# ottoesp-2s-wrover.net
KiCad netlist of a schematic drawn in EAGLE
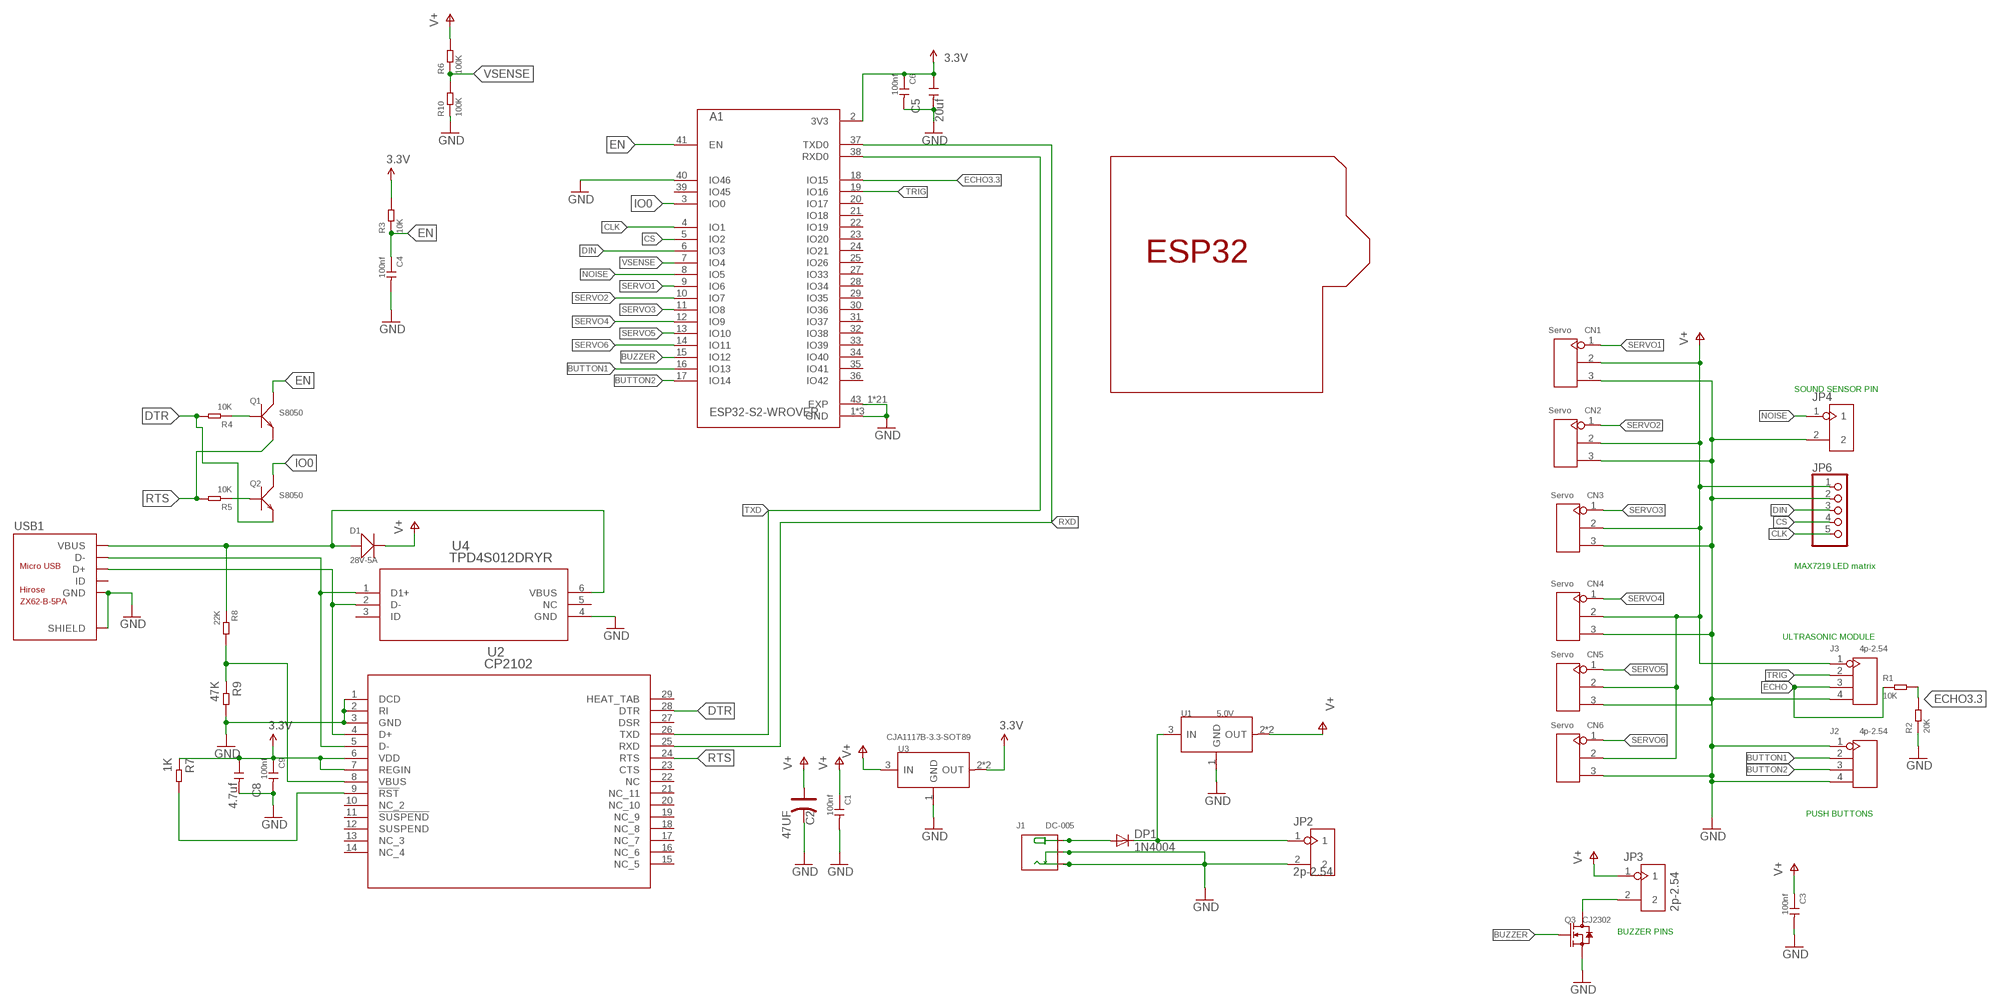
[diagram p0: schematic, sheet 1]

(export (version "E")
  (design (tool "Eeschema 10.0.6"))
  (components
    (comp (ref "A1")
      (value "ESP32-S2-WROVER")
      (footprint "eagle-import:MODULE_ESP32-S2-WROVER")
      (fields (field (name "MF") "Espressif Systems"))
      (libsource (lib "eagle-import") (part "ESP32-S2-WROVER"))
    )
    (comp (ref "C1")
      (value "100nf")
      (footprint "eagle-import:C0805")
      (fields (field (name "MPN") "CC0805KRX7R9BB104"))
      (libsource (lib "eagle-import") (part "CERAMIC-100NF-50V-10%-X7R(0805)"))
    )
    (comp (ref "C2")
      (value "47UF")
      (footprint "eagle-import:ELECTRO-SMD-C-6MM")
      (fields (field (name "MPN") "CS1E470M-CRE54"))
      (libsource (lib "eagle-import") (part "ALUMINUM-SMD-47UF-25V(D6.3-H5.3MM)"))
    )
    (comp (ref "C3")
      (value "100nf")
      (footprint "eagle-import:C0805")
      (fields (field (name "MPN") "CC0805KRX7R9BB104"))
      (libsource (lib "eagle-import") (part "Seeed-Capacitor_CERAMIC-100NF-50V-10%-X7R(0805)"))
    )
    (comp (ref "C4")
      (value "100nf")
      (footprint "eagle-import:C0805")
      (fields (field (name "MPN") "CC0805KRX7R9BB104"))
      (libsource (lib "eagle-import") (part "CERAMIC-100NF-50V-10%-X7R(0805)"))
    )
    (comp (ref "C5")
      (value "20uf")
      (footprint "eagle-import:C1206")
      (libsource (lib "eagle-import") (part "CERAMIC-22UF-16V-10%-X7R(1206)"))
    )
    (comp (ref "C6")
      (value "100nf")
      (footprint "eagle-import:C0805")
      (fields (field (name "MPN") "CC0805KRX7R9BB104"))
      (libsource (lib "eagle-import") (part "CERAMIC-100NF-50V-10%-X7R(0805)"))
    )
    (comp (ref "C8")
      (value "4.7uf")
      (footprint "eagle-import:C0805")
      (fields (field (name "MPN") "CC0805KKX5R8BB475"))
      (libsource (lib "eagle-import") (part "CERAMIC-4.7UF-25V-10%-X5R(0805)"))
    )
    (comp (ref "C9")
      (value "100nf")
      (footprint "eagle-import:C0805")
      (fields (field (name "MPN") "CC0805KRX7R9BB104"))
      (libsource (lib "eagle-import") (part "CERAMIC-100NF-50V-10%-X7R(0805)"))
    )
    (comp (ref "CN1")
      (value "Servo")
      (footprint "eagle-import:H3-2.54")
      (libsource (lib "eagle-import") (part "DIP-BLACK-MALE-HEADER-VERT(3P-2.54)"))
    )
    (comp (ref "CN2")
      (value "Servo")
      (footprint "eagle-import:H3-2.54")
      (libsource (lib "eagle-import") (part "DIP-BLACK-MALE-HEADER-VERT(3P-2.54)"))
    )
    (comp (ref "CN3")
      (value "Servo")
      (footprint "eagle-import:H3-2.54")
      (libsource (lib "eagle-import") (part "DIP-BLACK-MALE-HEADER-VERT(3P-2.54)"))
    )
    (comp (ref "CN4")
      (value "Servo")
      (footprint "eagle-import:H3-2.54")
      (libsource (lib "eagle-import") (part "DIP-BLACK-MALE-HEADER-VERT(3P-2.54)"))
    )
    (comp (ref "CN5")
      (value "Servo")
      (footprint "eagle-import:H3-2.54")
      (libsource (lib "eagle-import") (part "DIP-BLACK-MALE-HEADER-VERT(3P-2.54)"))
    )
    (comp (ref "CN6")
      (value "Servo")
      (footprint "eagle-import:H3-2.54")
      (libsource (lib "eagle-import") (part "DIP-BLACK-MALE-HEADER-VERT(3P-2.54)"))
    )
    (comp (ref "D1")
      (value "28V-5A")
      (footprint "eagle-import:DO-214AA")
      (fields (field (name "MPN") "SS54B"))
      (libsource (lib "eagle-import") (part "SMD-DIODE-SCHOTTKY-28V-5A(DO-214AA)"))
    )
    (comp (ref "DP1")
      (value "1N4004")
      (footprint "eagle-import:DO41-10")
      (libsource (lib "eagle-import") (part "1N4004"))
    )
    (comp (ref "J1")
      (value "DC-005")
      (footprint "eagle-import:DCJ3P-14.2X11.0X9.0MM")
      (libsource (lib "eagle-import") (part "CONN-POWER-JACK-2.1MM(DC-005)"))
    )
    (comp (ref "J2")
      (value "4p-2.54")
      (footprint "eagle-import:H4-2.54")
      (fields (field (name "MPN") "P125-1104A0BS116A1"))
      (libsource (lib "eagle-import") (part "DIP-BLACK-MALE-HEADER-VERT(4P-2.54)"))
    )
    (comp (ref "J3")
      (value "4p-2.54")
      (footprint "eagle-import:H4-2.54")
      (fields (field (name "MPN") "P125-1104A0BS116A1"))
      (libsource (lib "eagle-import") (part "DIP-BLACK-MALE-HEADER-VERT(4P-2.54)"))
    )
    (comp (ref "JP2")
      (value "2p-2.54")
      (footprint "eagle-import:H2-2.54")
      (fields (field (name "MPN") "P125-1102A0BS116A1"))
      (libsource (lib "eagle-import") (part "DIP-BLACK-MALE-HEADER-VERT(2P-2.54)"))
    )
    (comp (ref "JP3")
      (value "2p-2.54")
      (footprint "eagle-import:H2-2.54")
      (fields (field (name "MPN") "P125-1102A0BS116A1"))
      (libsource (lib "eagle-import") (part "DIP-BLACK-MALE-HEADER-VERT(2P-2.54)"))
    )
    (comp (ref "JP4")
      (value "2p-2.54")
      (footprint "eagle-import:H2-2.54")
      (fields (field (name "MPN") "P125-1102A0BS116A1"))
      (libsource (lib "eagle-import") (part "DIP-BLACK-MALE-HEADER-VERT(2P-2.54)"))
    )
    (comp (ref "JP6")
      (value "PINHD-1X5")
      (footprint "eagle-import:1X05")
      (libsource (lib "eagle-import") (part "PINHD-1X5"))
    )
    (comp (ref "Q1")
      (value "S8050")
      (footprint "eagle-import:SOT-23")
      (libsource (lib "eagle-import") (part "SMD-TRANSISTORS-NPN-25V-500MW-S8050(SOT-23)"))
    )
    (comp (ref "Q2")
      (value "S8050")
      (footprint "eagle-import:SOT-23")
      (libsource (lib "eagle-import") (part "SMD-TRANSISTORS-NPN-25V-500MW-S8050(SOT-23)"))
    )
    (comp (ref "Q3")
      (value "CJ2302")
      (footprint "eagle-import:SOT-23")
      (libsource (lib "eagle-import") (part "SMD-MOSFET-N-CH-20V-2.1A-CJ2302(SOT-23)"))
    )
    (comp (ref "R1")
      (value "10K")
      (footprint "eagle-import:R0805")
      (fields (field (name "MPN") "RC0805FR-0710KL"))
      (libsource (lib "eagle-import") (part "SMD-RES-10K-1%-1/8W(0805)"))
    )
    (comp (ref "R2")
      (value "20K")
      (footprint "eagle-import:R0805")
      (fields (field (name "MPN") "RC0805JR-071KL"))
      (libsource (lib "eagle-import") (part "SMD-RES-20K-5%-1/8W(0805)"))
    )
    (comp (ref "R3")
      (value "10K")
      (footprint "eagle-import:R0805")
      (fields (field (name "MPN") "RC0805FR-0710KL"))
      (libsource (lib "eagle-import") (part "SMD-RES-10K-1%-1/8W(0805)"))
    )
    (comp (ref "R4")
      (value "10K")
      (footprint "eagle-import:R0805")
      (fields (field (name "MPN") "RC0805FR-0710KL"))
      (libsource (lib "eagle-import") (part "SMD-RES-10K-1%-1/8W(0805)"))
    )
    (comp (ref "R5")
      (value "10K")
      (footprint "eagle-import:R0805")
      (fields (field (name "MPN") "RC0805FR-0710KL"))
      (libsource (lib "eagle-import") (part "SMD-RES-10K-1%-1/8W(0805)"))
    )
    (comp (ref "R6")
      (value "100K")
      (footprint "eagle-import:R0805")
      (fields (field (name "MPN") "RC0805JR-071KL"))
      (libsource (lib "eagle-import") (part "SMD-RES-100K-1%-1/8W(0805)"))
    )
    (comp (ref "R7")
      (value "1K")
      (footprint "eagle-import:R0805")
      (fields (field (name "MPN") "RC0805JR-071KL"))
      (libsource (lib "eagle-import") (part "SMD-RES-2K-1%-1/8W(0805)"))
    )
    (comp (ref "R8")
      (value "22K")
      (footprint "eagle-import:R0805")
      (fields (field (name "MPN") "RC0805JR-071KL"))
      (libsource (lib "eagle-import") (part "SMD-RES-22K-1%-1/8W(0805)"))
    )
    (comp (ref "R9")
      (value "47K")
      (footprint "eagle-import:R0603")
      (fields (field (name "MPN") "RC0603JR-0747KL"))
      (libsource (lib "eagle-import") (part "SMD-RES-47K-5%-1/10W(0603)"))
    )
    (comp (ref "R10")
      (value "100K")
      (footprint "eagle-import:R0805")
      (fields (field (name "MPN") "RC0805JR-071KL"))
      (libsource (lib "eagle-import") (part "SMD-RES-100K-1%-1/8W(0805)"))
    )
    (comp (ref "U$2")
      (value "ESP32_SHIELDSMALL")
      (footprint "eagle-import:ESP32_ARDUINOSHIELDSMALL")
      (libsource (lib "eagle-import") (part "ESP32_SHIELDSMALL"))
    )
    (comp (ref "U1")
      (value "5.0V")
      (footprint "eagle-import:SOT-223")
      (fields (field (name "MPN") "CJT1117-5.0"))
      (libsource (lib "eagle-import") (part "PMIC-CJT1117-5.0(SOT223)"))
    )
    (comp (ref "U2")
      (value "CP2102")
      (footprint "eagle-import:QFN28N5X5-0P5P")
      (libsource (lib "eagle-import") (part "CP2102"))
    )
    (comp (ref "U3")
      (value "CJA1117B-3.3-SOT89")
      (footprint "eagle-import:SOT-89")
      (fields (field (name "MPN") "CJA1117B-3.3"))
      (libsource (lib "eagle-import") (part "PMIC-CJA1117B-3.3(SOT-89)"))
    )
    (comp (ref "U4")
      (value "TPD4S012DRYR")
      (footprint "eagle-import:DRY6")
      (libsource (lib "eagle-import") (part "TPD4S012DRYR"))
    )
    (comp (ref "USB1")
      (value "ZX62-B-5PA")
      (footprint "eagle-import:MICRO-USB5+6P-SMD-0.65-AB")
      (libsource (lib "eagle-import") (part "MICRO-USB-SMD(ZX62-B-5PA)"))
    )
  )
  (nets
    (net (code "1") (name "3.3V") (class "Default")
      (node (ref "A1") (pin "2") (pinfunction "3V3_2") (pintype "power_in"))
      (node (ref "C5") (pin "1") (pinfunction "1_1") (pintype "passive"))
      (node (ref "C6") (pin "1") (pinfunction "1_1") (pintype "passive"))
      (node (ref "C8") (pin "1") (pinfunction "1_1") (pintype "passive"))
      (node (ref "C9") (pin "1") (pinfunction "1_1") (pintype "passive"))
      (node (ref "R3") (pin "2") (pinfunction "2_2") (pintype "passive"))
      (node (ref "R7") (pin "1") (pinfunction "1_1") (pintype "passive"))
      (node (ref "U2") (pin "6") (pinfunction "VDD_6") (pintype "passive"))
      (node (ref "U2") (pin "7") (pinfunction "REGIN_7") (pintype "passive"))
      (node (ref "U3") (pin "2") (pinfunction "OUT_2") (pintype "bidirectional"))
      (node (ref "U3") (pin "4") (pinfunction "OUT_4") (pintype "bidirectional"))
    )
    (net (code "2") (name "BUTTON1") (class "Default")
      (node (ref "A1") (pin "16") (pinfunction "IO13_16") (pintype "bidirectional"))
      (node (ref "J2") (pin "2") (pinfunction "P$2_2") (pintype "bidirectional"))
    )
    (net (code "3") (name "BUTTON2") (class "Default")
      (node (ref "A1") (pin "17") (pinfunction "IO14_17") (pintype "bidirectional"))
      (node (ref "J2") (pin "3") (pinfunction "P$3_3") (pintype "bidirectional"))
    )
    (net (code "4") (name "BUZZER") (class "Default")
      (node (ref "A1") (pin "15") (pinfunction "IO12_15") (pintype "bidirectional"))
      (node (ref "Q3") (pin "1") (pinfunction "G_1") (pintype "passive"))
    )
    (net (code "5") (name "CLK") (class "Default")
      (node (ref "A1") (pin "4") (pinfunction "IO1_4") (pintype "bidirectional"))
      (node (ref "JP6") (pin "5") (pinfunction "5_5") (pintype "passive"))
    )
    (net (code "6") (name "CS") (class "Default")
      (node (ref "A1") (pin "5") (pinfunction "IO2_5") (pintype "bidirectional"))
      (node (ref "JP6") (pin "4") (pinfunction "4_4") (pintype "passive"))
    )
    (net (code "7") (name "DIN") (class "Default")
      (node (ref "A1") (pin "6") (pinfunction "IO3_6") (pintype "bidirectional"))
      (node (ref "JP6") (pin "3") (pinfunction "3_3") (pintype "passive"))
    )
    (net (code "8") (name "DTR") (class "Default")
      (node (ref "Q2") (pin "2") (pinfunction "E_2") (pintype "passive"))
      (node (ref "R4") (pin "2") (pinfunction "2_2") (pintype "passive"))
      (node (ref "U2") (pin "28") (pinfunction "DTR_28") (pintype "passive"))
    )
    (net (code "9") (name "ECHO") (class "Default")
      (node (ref "J3") (pin "3") (pinfunction "P$3_3") (pintype "bidirectional"))
      (node (ref "R1") (pin "1") (pinfunction "1_1") (pintype "passive"))
    )
    (net (code "10") (name "ECHO3.3") (class "Default")
      (node (ref "A1") (pin "18") (pinfunction "IO15_18") (pintype "bidirectional"))
      (node (ref "R1") (pin "2") (pinfunction "2_2") (pintype "passive"))
      (node (ref "R2") (pin "2") (pinfunction "2_2") (pintype "passive"))
    )
    (net (code "11") (name "EN") (class "Default")
      (node (ref "A1") (pin "41") (pinfunction "EN_41") (pintype "input"))
      (node (ref "C4") (pin "1") (pinfunction "1_1") (pintype "passive"))
      (node (ref "Q1") (pin "3") (pinfunction "C_3") (pintype "passive"))
      (node (ref "R3") (pin "1") (pinfunction "1_1") (pintype "passive"))
    )
    (net (code "12") (name "GND") (class "Default")
      (node (ref "A1") (pin "1") (pinfunction "GND_1") (pintype "power_in"))
      (node (ref "A1") (pin "26") (pinfunction "GND_26") (pintype "power_in"))
      (node (ref "A1") (pin "40") (pinfunction "IO46_40") (pintype "input"))
      (node (ref "A1") (pin "42") (pinfunction "GND_42") (pintype "power_in"))
      (node (ref "A1") (pin "43_1") (pinfunction "EXP_43_1") (pintype "power_in"))
      (node (ref "A1") (pin "43_10") (pinfunction "EXP_43_10") (pintype "power_in"))
      (node (ref "A1") (pin "43_11") (pinfunction "EXP_43_11") (pintype "power_in"))
      (node (ref "A1") (pin "43_12") (pinfunction "EXP_43_12") (pintype "power_in"))
      (node (ref "A1") (pin "43_13") (pinfunction "EXP_43_13") (pintype "power_in"))
      (node (ref "A1") (pin "43_14") (pinfunction "EXP_43_14") (pintype "power_in"))
      (node (ref "A1") (pin "43_15") (pinfunction "EXP_43_15") (pintype "power_in"))
      (node (ref "A1") (pin "43_16") (pinfunction "EXP_43_16") (pintype "power_in"))
      (node (ref "A1") (pin "43_17") (pinfunction "EXP_43_17") (pintype "power_in"))
      (node (ref "A1") (pin "43_18") (pinfunction "EXP_43_18") (pintype "power_in"))
      (node (ref "A1") (pin "43_19") (pinfunction "EXP_43_19") (pintype "power_in"))
      (node (ref "A1") (pin "43_2") (pinfunction "EXP_43_2") (pintype "power_in"))
      (node (ref "A1") (pin "43_20") (pinfunction "EXP_43_20") (pintype "power_in"))
      (node (ref "A1") (pin "43_21") (pinfunction "EXP_43_21") (pintype "power_in"))
      (node (ref "A1") (pin "43_3") (pinfunction "EXP_43_3") (pintype "power_in"))
      (node (ref "A1") (pin "43_4") (pinfunction "EXP_43_4") (pintype "power_in"))
      (node (ref "A1") (pin "43_5") (pinfunction "EXP_43_5") (pintype "power_in"))
      (node (ref "A1") (pin "43_6") (pinfunction "EXP_43_6") (pintype "power_in"))
      (node (ref "A1") (pin "43_7") (pinfunction "EXP_43_7") (pintype "power_in"))
      (node (ref "A1") (pin "43_8") (pinfunction "EXP_43_8") (pintype "power_in"))
      (node (ref "A1") (pin "43_9") (pinfunction "EXP_43_9") (pintype "power_in"))
      (node (ref "C1") (pin "2") (pinfunction "2_2") (pintype "passive"))
      (node (ref "C2") (pin "-") (pinfunction "-_-") (pintype "passive"))
      (node (ref "C3") (pin "2") (pinfunction "2_2") (pintype "passive"))
      (node (ref "C4") (pin "2") (pinfunction "2_2") (pintype "passive"))
      (node (ref "C5") (pin "2") (pinfunction "2_2") (pintype "passive"))
      (node (ref "C6") (pin "2") (pinfunction "2_2") (pintype "passive"))
      (node (ref "C8") (pin "2") (pinfunction "2_2") (pintype "passive"))
      (node (ref "C9") (pin "2") (pinfunction "2_2") (pintype "passive"))
      (node (ref "CN1") (pin "3") (pinfunction "P$3_3") (pintype "bidirectional"))
      (node (ref "CN2") (pin "3") (pinfunction "P$3_3") (pintype "bidirectional"))
      (node (ref "CN3") (pin "3") (pinfunction "P$3_3") (pintype "bidirectional"))
      (node (ref "CN4") (pin "3") (pinfunction "P$3_3") (pintype "bidirectional"))
      (node (ref "CN5") (pin "3") (pinfunction "P$3_3") (pintype "bidirectional"))
      (node (ref "CN6") (pin "3") (pinfunction "P$3_3") (pintype "bidirectional"))
      (node (ref "J1") (pin "-1") (pinfunction "-_-1") (pintype "bidirectional"))
      (node (ref "J1") (pin "-2") (pinfunction "CDN_-2") (pintype "bidirectional"))
      (node (ref "J2") (pin "1") (pinfunction "P$1_1") (pintype "bidirectional"))
      (node (ref "J2") (pin "4") (pinfunction "P$4_4") (pintype "bidirectional"))
      (node (ref "J3") (pin "4") (pinfunction "P$4_4") (pintype "bidirectional"))
      (node (ref "JP2") (pin "2") (pinfunction "2_2") (pintype "bidirectional"))
      (node (ref "JP4") (pin "2") (pinfunction "2_2") (pintype "bidirectional"))
      (node (ref "JP6") (pin "2") (pinfunction "2_2") (pintype "passive"))
      (node (ref "Q3") (pin "2") (pinfunction "S_2") (pintype "passive"))
      (node (ref "R10") (pin "1") (pinfunction "1_1") (pintype "passive"))
      (node (ref "R2") (pin "1") (pinfunction "1_1") (pintype "passive"))
      (node (ref "R9") (pin "2") (pinfunction "2_2") (pintype "passive"))
      (node (ref "U1") (pin "1") (pinfunction "GND_1") (pintype "bidirectional"))
      (node (ref "U2") (pin "1") (pinfunction "DCD_1") (pintype "passive"))
      (node (ref "U2") (pin "2") (pinfunction "RI_2") (pintype "passive"))
      (node (ref "U2") (pin "3") (pinfunction "GND_3") (pintype "passive"))
      (node (ref "U3") (pin "1") (pinfunction "GND_1") (pintype "bidirectional"))
      (node (ref "U4") (pin "4") (pinfunction "GND_4") (pintype "power_in"))
      (node (ref "USB1") (pin "5") (pinfunction "GND_5") (pintype "power_in"))
      (node (ref "USB1") (pin "P1") (pinfunction "SHIELD_P1") (pintype "power_in"))
      (node (ref "USB1") (pin "P2") (pinfunction "SHIELD_P2") (pintype "power_in"))
      (node (ref "USB1") (pin "P3") (pinfunction "SHIELD_P3") (pintype "power_in"))
      (node (ref "USB1") (pin "P4") (pinfunction "SHIELD_P4") (pintype "power_in"))
      (node (ref "USB1") (pin "P5") (pinfunction "SHIELD_P5") (pintype "power_in"))
      (node (ref "USB1") (pin "P6") (pinfunction "SHIELD_P6") (pintype "power_in"))
    )
    (net (code "13") (name "IO0") (class "Default")
      (node (ref "A1") (pin "3") (pinfunction "IO0_3") (pintype "bidirectional"))
      (node (ref "Q2") (pin "3") (pinfunction "C_3") (pintype "passive"))
    )
    (net (code "14") (name "NOISE") (class "Default")
      (node (ref "A1") (pin "8") (pinfunction "IO5_8") (pintype "bidirectional"))
      (node (ref "JP4") (pin "1") (pinfunction "1_1") (pintype "bidirectional"))
    )
    (net (code "15") (name "Net-(DP1-PadA)") (class "Default")
      (node (ref "DP1") (pin "A") (pinfunction "A_A") (pintype "passive"))
      (node (ref "J1") (pin "+") (pinfunction "+_+") (pintype "bidirectional"))
    )
    (net (code "16") (name "Net-(Q1-B)") (class "Default")
      (node (ref "Q1") (pin "1") (pinfunction "B_1") (pintype "passive"))
      (node (ref "R4") (pin "1") (pinfunction "1_1") (pintype "passive"))
    )
    (net (code "17") (name "Net-(Q2-B)") (class "Default")
      (node (ref "Q2") (pin "1") (pinfunction "B_1") (pintype "passive"))
      (node (ref "R5") (pin "1") (pinfunction "1_1") (pintype "passive"))
    )
    (net (code "18") (name "Net-(Q3-D)") (class "Default")
      (node (ref "JP3") (pin "2") (pinfunction "2_2") (pintype "bidirectional"))
      (node (ref "Q3") (pin "3") (pinfunction "D_3") (pintype "passive"))
    )
    (net (code "19") (name "Net-(U1-IN)") (class "Default")
      (node (ref "DP1") (pin "C") (pinfunction "C_C") (pintype "passive"))
      (node (ref "JP2") (pin "1") (pinfunction "1_1") (pintype "bidirectional"))
      (node (ref "U1") (pin "3") (pinfunction "IN_3") (pintype "bidirectional"))
    )
    (net (code "20") (name "Net-(U2-D+)") (class "Default")
      (node (ref "U2") (pin "4") (pinfunction "D+_4") (pintype "passive"))
      (node (ref "U4") (pin "2") (pinfunction "D-_2") (pintype "passive"))
      (node (ref "USB1") (pin "3") (pinfunction "D+_3") (pintype "bidirectional"))
    )
    (net (code "21") (name "Net-(U2-D-)") (class "Default")
      (node (ref "U2") (pin "5") (pinfunction "D-_5") (pintype "passive"))
      (node (ref "U4") (pin "1") (pinfunction "D1+_1") (pintype "passive"))
      (node (ref "USB1") (pin "2") (pinfunction "D-_2") (pintype "bidirectional"))
    )
    (net (code "22") (name "Net-(U2-VBUS)") (class "Default")
      (node (ref "R8") (pin "2") (pinfunction "2_2") (pintype "passive"))
      (node (ref "R9") (pin "1") (pinfunction "1_1") (pintype "passive"))
      (node (ref "U2") (pin "8") (pinfunction "VBUS_8") (pintype "passive"))
    )
    (net (code "23") (name "Net-(U2-~{RST})") (class "Default")
      (node (ref "R7") (pin "2") (pinfunction "2_2") (pintype "passive"))
      (node (ref "U2") (pin "9") (pinfunction "~{RST}_9") (pintype "passive"))
    )
    (net (code "24") (name "Net-(U4-VBUS)") (class "Default")
      (node (ref "D1") (pin "+") (pinfunction "+_+") (pintype "passive"))
      (node (ref "R8") (pin "1") (pinfunction "1_1") (pintype "passive"))
      (node (ref "U4") (pin "6") (pinfunction "VBUS_6") (pintype "power_in"))
      (node (ref "USB1") (pin "1") (pinfunction "VBUS_1") (pintype "power_in"))
    )
    (net (code "25") (name "RTS") (class "Default")
      (node (ref "Q1") (pin "2") (pinfunction "E_2") (pintype "passive"))
      (node (ref "R5") (pin "2") (pinfunction "2_2") (pintype "passive"))
      (node (ref "U2") (pin "24") (pinfunction "RTS_24") (pintype "passive"))
    )
    (net (code "26") (name "RXD") (class "Default")
      (node (ref "A1") (pin "37") (pinfunction "TXD0_37") (pintype "bidirectional"))
      (node (ref "U2") (pin "25") (pinfunction "RXD_25") (pintype "passive"))
    )
    (net (code "27") (name "SERVO1") (class "Default")
      (node (ref "A1") (pin "9") (pinfunction "IO6_9") (pintype "bidirectional"))
      (node (ref "CN1") (pin "1") (pinfunction "P$1_1") (pintype "bidirectional"))
    )
    (net (code "28") (name "SERVO2") (class "Default")
      (node (ref "A1") (pin "10") (pinfunction "IO7_10") (pintype "bidirectional"))
      (node (ref "CN2") (pin "1") (pinfunction "P$1_1") (pintype "bidirectional"))
    )
    (net (code "29") (name "SERVO3") (class "Default")
      (node (ref "A1") (pin "11") (pinfunction "IO8_11") (pintype "bidirectional"))
      (node (ref "CN3") (pin "1") (pinfunction "P$1_1") (pintype "bidirectional"))
    )
    (net (code "30") (name "SERVO4") (class "Default")
      (node (ref "A1") (pin "12") (pinfunction "IO9_12") (pintype "bidirectional"))
      (node (ref "CN4") (pin "1") (pinfunction "P$1_1") (pintype "bidirectional"))
    )
    (net (code "31") (name "SERVO5") (class "Default")
      (node (ref "A1") (pin "13") (pinfunction "IO10_13") (pintype "bidirectional"))
      (node (ref "CN5") (pin "1") (pinfunction "P$1_1") (pintype "bidirectional"))
    )
    (net (code "32") (name "SERVO6") (class "Default")
      (node (ref "A1") (pin "14") (pinfunction "IO11_14") (pintype "bidirectional"))
      (node (ref "CN6") (pin "1") (pinfunction "P$1_1") (pintype "bidirectional"))
    )
    (net (code "33") (name "TRIG") (class "Default")
      (node (ref "A1") (pin "19") (pinfunction "IO16_19") (pintype "bidirectional"))
      (node (ref "J3") (pin "2") (pinfunction "P$2_2") (pintype "bidirectional"))
    )
    (net (code "34") (name "TXD") (class "Default")
      (node (ref "A1") (pin "38") (pinfunction "RXD0_38") (pintype "bidirectional"))
      (node (ref "U2") (pin "26") (pinfunction "TXD_26") (pintype "passive"))
    )
    (net (code "35") (name "V+") (class "Default")
      (node (ref "C1") (pin "1") (pinfunction "1_1") (pintype "passive"))
      (node (ref "C2") (pin "+") (pinfunction "+_+") (pintype "passive"))
      (node (ref "C3") (pin "1") (pinfunction "1_1") (pintype "passive"))
      (node (ref "CN1") (pin "2") (pinfunction "P$2_2") (pintype "bidirectional"))
      (node (ref "CN2") (pin "2") (pinfunction "P$2_2") (pintype "bidirectional"))
      (node (ref "CN3") (pin "2") (pinfunction "P$2_2") (pintype "bidirectional"))
      (node (ref "CN4") (pin "2") (pinfunction "P$2_2") (pintype "bidirectional"))
      (node (ref "CN5") (pin "2") (pinfunction "P$2_2") (pintype "bidirectional"))
      (node (ref "CN6") (pin "2") (pinfunction "P$2_2") (pintype "bidirectional"))
      (node (ref "D1") (pin "-") (pinfunction "-_-") (pintype "passive"))
      (node (ref "J3") (pin "1") (pinfunction "P$1_1") (pintype "bidirectional"))
      (node (ref "JP3") (pin "1") (pinfunction "1_1") (pintype "bidirectional"))
      (node (ref "JP6") (pin "1") (pinfunction "1_1") (pintype "passive"))
      (node (ref "R6") (pin "2") (pinfunction "2_2") (pintype "passive"))
      (node (ref "U1") (pin "2") (pinfunction "OUT_2") (pintype "bidirectional"))
      (node (ref "U1") (pin "TER") (pinfunction "OUT_TER") (pintype "bidirectional"))
      (node (ref "U3") (pin "3") (pinfunction "IN_3") (pintype "bidirectional"))
    )
    (net (code "36") (name "VSENSE") (class "Default")
      (node (ref "A1") (pin "7") (pinfunction "IO4_7") (pintype "bidirectional"))
      (node (ref "R10") (pin "2") (pinfunction "2_2") (pintype "passive"))
      (node (ref "R6") (pin "1") (pinfunction "1_1") (pintype "passive"))
    )
    (net (code "37") (name "unconnected-(A1-IO17-Pad20)") (class "Default")
      (node (ref "A1") (pin "20") (pinfunction "IO17_20") (pintype "bidirectional"))
    )
    (net (code "38") (name "unconnected-(A1-IO18-Pad21)") (class "Default")
      (node (ref "A1") (pin "21") (pinfunction "IO18_21") (pintype "bidirectional"))
    )
    (net (code "39") (name "unconnected-(A1-IO19-Pad22)") (class "Default")
      (node (ref "A1") (pin "22") (pinfunction "IO19_22") (pintype "bidirectional"))
    )
    (net (code "40") (name "unconnected-(A1-IO20-Pad23)") (class "Default")
      (node (ref "A1") (pin "23") (pinfunction "IO20_23") (pintype "bidirectional"))
    )
    (net (code "41") (name "unconnected-(A1-IO21-Pad24)") (class "Default")
      (node (ref "A1") (pin "24") (pinfunction "IO21_24") (pintype "bidirectional"))
    )
    (net (code "42") (name "unconnected-(A1-IO26-Pad25)") (class "Default")
      (node (ref "A1") (pin "25") (pinfunction "IO26_25") (pintype "bidirectional"))
    )
    (net (code "43") (name "unconnected-(A1-IO33-Pad27)") (class "Default")
      (node (ref "A1") (pin "27") (pinfunction "IO33_27") (pintype "bidirectional"))
    )
    (net (code "44") (name "unconnected-(A1-IO34-Pad28)") (class "Default")
      (node (ref "A1") (pin "28") (pinfunction "IO34_28") (pintype "input"))
    )
    (net (code "45") (name "unconnected-(A1-IO35-Pad29)") (class "Default")
      (node (ref "A1") (pin "29") (pinfunction "IO35_29") (pintype "input"))
    )
    (net (code "46") (name "unconnected-(A1-IO36-Pad30)") (class "Default")
      (node (ref "A1") (pin "30") (pinfunction "IO36_30") (pintype "bidirectional"))
    )
    (net (code "47") (name "unconnected-(A1-IO37-Pad31)") (class "Default")
      (node (ref "A1") (pin "31") (pinfunction "IO37_31") (pintype "bidirectional"))
    )
    (net (code "48") (name "unconnected-(A1-IO38-Pad32)") (class "Default")
      (node (ref "A1") (pin "32") (pinfunction "IO38_32") (pintype "bidirectional"))
    )
    (net (code "49") (name "unconnected-(A1-IO39-Pad33)") (class "Default")
      (node (ref "A1") (pin "33") (pinfunction "IO39_33") (pintype "bidirectional"))
    )
    (net (code "50") (name "unconnected-(A1-IO40-Pad34)") (class "Default")
      (node (ref "A1") (pin "34") (pinfunction "IO40_34") (pintype "bidirectional"))
    )
    (net (code "51") (name "unconnected-(A1-IO41-Pad35)") (class "Default")
      (node (ref "A1") (pin "35") (pinfunction "IO41_35") (pintype "bidirectional"))
    )
    (net (code "52") (name "unconnected-(A1-IO42-Pad36)") (class "Default")
      (node (ref "A1") (pin "36") (pinfunction "IO42_36") (pintype "bidirectional"))
    )
    (net (code "53") (name "unconnected-(A1-IO45-Pad39)") (class "Default")
      (node (ref "A1") (pin "39") (pinfunction "IO45_39") (pintype "bidirectional"))
    )
    (net (code "54") (name "unconnected-(U2-CTS-Pad23)") (class "Default")
      (node (ref "U2") (pin "23") (pinfunction "CTS_23") (pintype "passive"))
    )
    (net (code "55") (name "unconnected-(U2-DSR-Pad27)") (class "Default")
      (node (ref "U2") (pin "27") (pinfunction "DSR_27") (pintype "passive"))
    )
    (net (code "56") (name "unconnected-(U2-HEAT_TAB-Pad29)") (class "Default")
      (node (ref "U2") (pin "29") (pinfunction "HEAT_TAB_29") (pintype "passive"))
    )
    (net (code "57") (name "unconnected-(U2-NC-Pad22)") (class "Default")
      (node (ref "U2") (pin "22") (pinfunction "NC_22") (pintype "passive"))
    )
    (net (code "58") (name "unconnected-(U2-NC_2-Pad10)") (class "Default")
      (node (ref "U2") (pin "10") (pinfunction "NC_2_10") (pintype "passive"))
    )
    (net (code "59") (name "unconnected-(U2-NC_3-Pad13)") (class "Default")
      (node (ref "U2") (pin "13") (pinfunction "NC_3_13") (pintype "passive"))
    )
    (net (code "60") (name "unconnected-(U2-NC_4-Pad14)") (class "Default")
      (node (ref "U2") (pin "14") (pinfunction "NC_4_14") (pintype "passive"))
    )
    (net (code "61") (name "unconnected-(U2-NC_5-Pad15)") (class "Default")
      (node (ref "U2") (pin "15") (pinfunction "NC_5_15") (pintype "passive"))
    )
    (net (code "62") (name "unconnected-(U2-NC_6-Pad16)") (class "Default")
      (node (ref "U2") (pin "16") (pinfunction "NC_6_16") (pintype "passive"))
    )
    (net (code "63") (name "unconnected-(U2-NC_7-Pad17)") (class "Default")
      (node (ref "U2") (pin "17") (pinfunction "NC_7_17") (pintype "passive"))
    )
    (net (code "64") (name "unconnected-(U2-NC_8-Pad18)") (class "Default")
      (node (ref "U2") (pin "18") (pinfunction "NC_8_18") (pintype "passive"))
    )
    (net (code "65") (name "unconnected-(U2-NC_9-Pad19)") (class "Default")
      (node (ref "U2") (pin "19") (pinfunction "NC_9_19") (pintype "passive"))
    )
    (net (code "66") (name "unconnected-(U2-NC_10-Pad20)") (class "Default")
      (node (ref "U2") (pin "20") (pinfunction "NC_10_20") (pintype "passive"))
    )
    (net (code "67") (name "unconnected-(U2-NC_11-Pad21)") (class "Default")
      (node (ref "U2") (pin "21") (pinfunction "NC_11_21") (pintype "passive"))
    )
    (net (code "68") (name "unconnected-(U2-SUSPEND-Pad12)") (class "Default")
      (node (ref "U2") (pin "12") (pinfunction "SUSPEND_12") (pintype "passive"))
    )
    (net (code "69") (name "unconnected-(U2-~{SUSPEND}-Pad11)") (class "Default")
      (node (ref "U2") (pin "11") (pinfunction "~{SUSPEND}_11") (pintype "passive"))
    )
    (net (code "70") (name "unconnected-(U4-ID-Pad3)") (class "Default")
      (node (ref "U4") (pin "3") (pinfunction "ID_3") (pintype "passive"))
    )
    (net (code "71") (name "unconnected-(U4-NC-Pad5)") (class "Default")
      (node (ref "U4") (pin "5") (pinfunction "NC_5") (pintype "no_connect"))
    )
    (net (code "72") (name "unconnected-(USB1-ID-Pad4)") (class "Default")
      (node (ref "USB1") (pin "4") (pinfunction "ID_4") (pintype "bidirectional"))
    )
  )
)
